# dlp_vco_v1_1_4_pnl.net
KiCad netlist of a schematic drawn in EAGLE
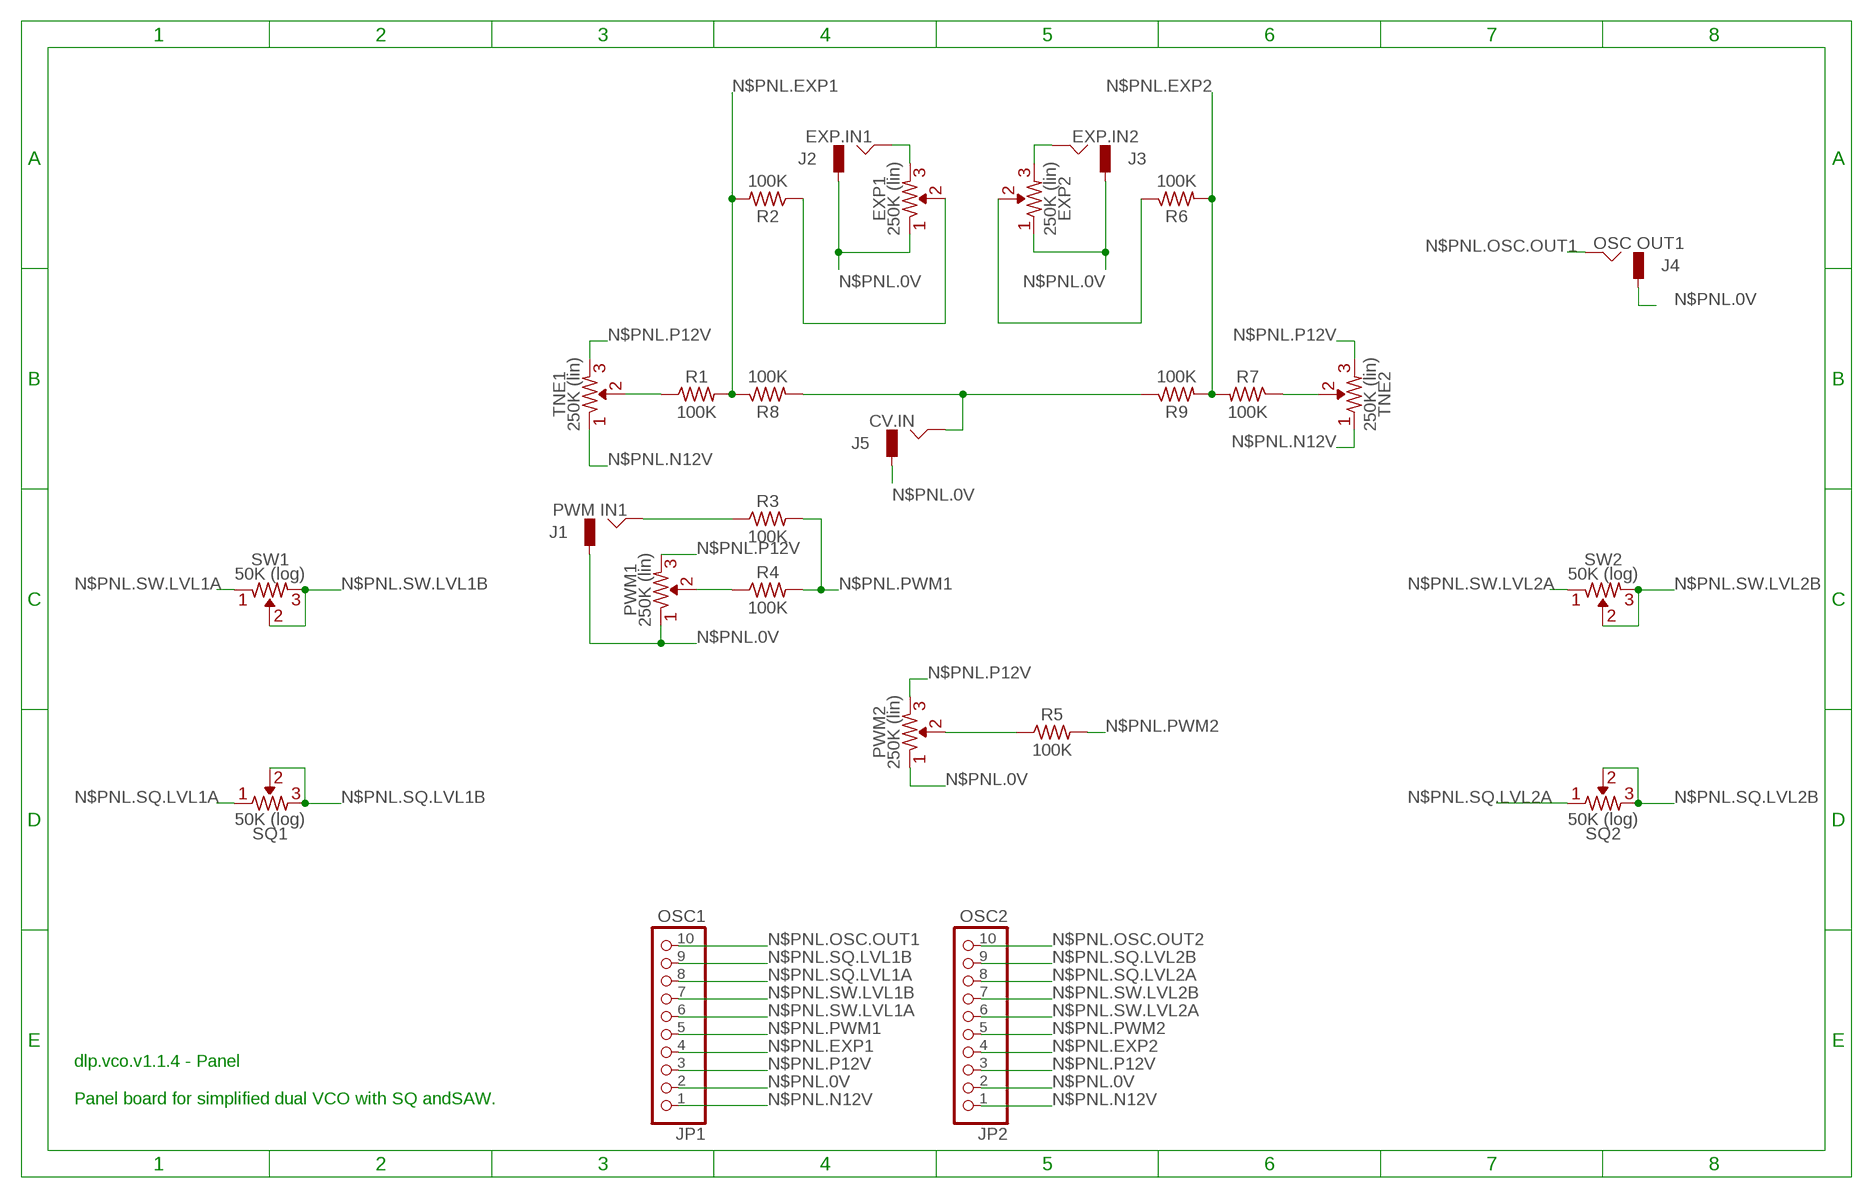
[diagram p0: schematic, sheet 1]

(export (version "E")
  (design (tool "Eeschema 10.0.6"))
  (components
    (comp (ref "EXP1")
      (value "250K (lin)")
      (footprint "eagle-import:R-VAR")
      (libsource (lib "eagle-import") (part "R-VAR"))
    )
    (comp (ref "EXP2")
      (value "250K (lin)")
      (footprint "eagle-import:R-VAR")
      (libsource (lib "eagle-import") (part "R-VAR"))
    )
    (comp (ref "J1")
      (value "PWM IN1")
      (footprint "eagle-import:JACK-M")
      (libsource (lib "eagle-import") (part "JACK-M"))
    )
    (comp (ref "J2")
      (value "EXP.IN1")
      (footprint "eagle-import:JACK-M")
      (libsource (lib "eagle-import") (part "JACK-M"))
    )
    (comp (ref "J3")
      (value "EXP.IN2")
      (footprint "eagle-import:JACK-M")
      (libsource (lib "eagle-import") (part "JACK-M"))
    )
    (comp (ref "J4")
      (value "OSC OUT1")
      (footprint "eagle-import:JACK-M")
      (libsource (lib "eagle-import") (part "JACK-M"))
    )
    (comp (ref "J5")
      (value "CV.IN")
      (footprint "eagle-import:JACK-M")
      (libsource (lib "eagle-import") (part "JACK-M"))
    )
    (comp (ref "JP1")
      (value "OSC1")
      (footprint "eagle-import:1X10")
      (libsource (lib "eagle-import") (part "PINHD-1X10"))
    )
    (comp (ref "JP2")
      (value "OSC2")
      (footprint "eagle-import:1X10")
      (libsource (lib "eagle-import") (part "PINHD-1X10"))
    )
    (comp (ref "PWM1")
      (value "250K (lin)")
      (footprint "eagle-import:R-VAR")
      (libsource (lib "eagle-import") (part "R-VAR"))
    )
    (comp (ref "PWM2")
      (value "250K (lin)")
      (footprint "eagle-import:R-VAR")
      (libsource (lib "eagle-import") (part "R-VAR"))
    )
    (comp (ref "R1")
      (value "100K")
      (footprint "eagle-import:0309_10")
      (libsource (lib "eagle-import") (part "R0309/10"))
    )
    (comp (ref "R2")
      (value "100K")
      (footprint "eagle-import:0309_10")
      (libsource (lib "eagle-import") (part "R0309/10"))
    )
    (comp (ref "R3")
      (value "100K")
      (footprint "eagle-import:0309_10")
      (libsource (lib "eagle-import") (part "R0309/10"))
    )
    (comp (ref "R4")
      (value "100K")
      (footprint "eagle-import:0309_10")
      (libsource (lib "eagle-import") (part "R0309/10"))
    )
    (comp (ref "R5")
      (value "100K")
      (footprint "eagle-import:0309_10")
      (libsource (lib "eagle-import") (part "R0309/10"))
    )
    (comp (ref "R6")
      (value "100K")
      (footprint "eagle-import:0309_10")
      (libsource (lib "eagle-import") (part "R0309/10"))
    )
    (comp (ref "R7")
      (value "100K")
      (footprint "eagle-import:0309_10")
      (libsource (lib "eagle-import") (part "R0309/10"))
    )
    (comp (ref "R8")
      (value "100K")
      (footprint "eagle-import:0309_10")
      (libsource (lib "eagle-import") (part "R0309/10"))
    )
    (comp (ref "R9")
      (value "100K")
      (footprint "eagle-import:0309_10")
      (libsource (lib "eagle-import") (part "R0309/10"))
    )
    (comp (ref "SQ1")
      (value "50K (log)")
      (footprint "eagle-import:R-VAR")
      (libsource (lib "eagle-import") (part "R-VAR"))
    )
    (comp (ref "SQ2")
      (value "50K (log)")
      (footprint "eagle-import:R-VAR")
      (libsource (lib "eagle-import") (part "R-VAR"))
    )
    (comp (ref "SW1")
      (value "50K (log)")
      (footprint "eagle-import:R-VAR")
      (libsource (lib "eagle-import") (part "R-VAR"))
    )
    (comp (ref "SW2")
      (value "50K (log)")
      (footprint "eagle-import:R-VAR")
      (libsource (lib "eagle-import") (part "R-VAR"))
    )
    (comp (ref "TNE1")
      (value "250K (lin)")
      (footprint "eagle-import:R-VAR")
      (libsource (lib "eagle-import") (part "R-VAR"))
    )
    (comp (ref "TNE2")
      (value "250K (lin)")
      (footprint "eagle-import:R-VAR")
      (libsource (lib "eagle-import") (part "R-VAR"))
    )
  )
  (nets
    (net (code "1") (name "/N$PNL.0V") (class "Default")
      (node (ref "EXP1") (pin "R1") (pinfunction "1_R1") (pintype "passive"))
      (node (ref "EXP2") (pin "R1") (pinfunction "1_R1") (pintype "passive"))
      (node (ref "J1") (pin "GND") (pinfunction "GND_GND") (pintype "bidirectional"))
      (node (ref "J2") (pin "GND") (pinfunction "GND_GND") (pintype "bidirectional"))
      (node (ref "J3") (pin "GND") (pinfunction "GND_GND") (pintype "bidirectional"))
      (node (ref "J4") (pin "GND") (pinfunction "GND_GND") (pintype "bidirectional"))
      (node (ref "J5") (pin "GND") (pinfunction "GND_GND") (pintype "bidirectional"))
      (node (ref "JP1") (pin "2") (pinfunction "2_2") (pintype "passive"))
      (node (ref "JP2") (pin "2") (pinfunction "2_2") (pintype "passive"))
      (node (ref "PWM1") (pin "R1") (pinfunction "1_R1") (pintype "passive"))
      (node (ref "PWM2") (pin "R1") (pinfunction "1_R1") (pintype "passive"))
    )
    (net (code "2") (name "/N$PNL.EXP1") (class "Default")
      (node (ref "JP1") (pin "4") (pinfunction "4_4") (pintype "passive"))
      (node (ref "R1") (pin "2") (pinfunction "2_2") (pintype "passive"))
      (node (ref "R2") (pin "2") (pinfunction "2_2") (pintype "passive"))
      (node (ref "R8") (pin "1") (pinfunction "1_1") (pintype "passive"))
    )
    (net (code "3") (name "/N$PNL.EXP2") (class "Default")
      (node (ref "JP2") (pin "4") (pinfunction "4_4") (pintype "passive"))
      (node (ref "R6") (pin "2") (pinfunction "2_2") (pintype "passive"))
      (node (ref "R7") (pin "2") (pinfunction "2_2") (pintype "passive"))
      (node (ref "R9") (pin "2") (pinfunction "2_2") (pintype "passive"))
    )
    (net (code "4") (name "/N$PNL.N12V") (class "Default")
      (node (ref "JP1") (pin "1") (pinfunction "1_1") (pintype "passive"))
      (node (ref "JP2") (pin "1") (pinfunction "1_1") (pintype "passive"))
      (node (ref "TNE1") (pin "R1") (pinfunction "1_R1") (pintype "passive"))
      (node (ref "TNE2") (pin "R1") (pinfunction "1_R1") (pintype "passive"))
    )
    (net (code "5") (name "/N$PNL.OSC.OUT1") (class "Default")
      (node (ref "J4") (pin "HOT") (pinfunction "HOT_HOT") (pintype "bidirectional"))
      (node (ref "JP1") (pin "10") (pinfunction "10_10") (pintype "passive"))
    )
    (net (code "6") (name "/N$PNL.OSC.OUT2") (class "Default")
      (node (ref "JP2") (pin "10") (pinfunction "10_10") (pintype "passive"))
    )
    (net (code "7") (name "/N$PNL.P12V") (class "Default")
      (node (ref "JP1") (pin "3") (pinfunction "3_3") (pintype "passive"))
      (node (ref "JP2") (pin "3") (pinfunction "3_3") (pintype "passive"))
      (node (ref "PWM1") (pin "R2") (pinfunction "2_R2") (pintype "passive"))
      (node (ref "PWM2") (pin "R2") (pinfunction "2_R2") (pintype "passive"))
      (node (ref "TNE1") (pin "R2") (pinfunction "2_R2") (pintype "passive"))
      (node (ref "TNE2") (pin "R2") (pinfunction "2_R2") (pintype "passive"))
    )
    (net (code "8") (name "/N$PNL.PWM1") (class "Default")
      (node (ref "JP1") (pin "5") (pinfunction "5_5") (pintype "passive"))
      (node (ref "R3") (pin "2") (pinfunction "2_2") (pintype "passive"))
      (node (ref "R4") (pin "2") (pinfunction "2_2") (pintype "passive"))
    )
    (net (code "9") (name "/N$PNL.PWM2") (class "Default")
      (node (ref "JP2") (pin "5") (pinfunction "5_5") (pintype "passive"))
      (node (ref "R5") (pin "2") (pinfunction "2_2") (pintype "passive"))
    )
    (net (code "10") (name "/N$PNL.SQ.LVL1A") (class "Default")
      (node (ref "JP1") (pin "8") (pinfunction "8_8") (pintype "passive"))
      (node (ref "SQ1") (pin "R1") (pinfunction "1_R1") (pintype "passive"))
    )
    (net (code "11") (name "/N$PNL.SQ.LVL1B") (class "Default")
      (node (ref "JP1") (pin "9") (pinfunction "9_9") (pintype "passive"))
      (node (ref "SQ1") (pin "R2") (pinfunction "2_R2") (pintype "passive"))
      (node (ref "SQ1") (pin "VAR") (pinfunction "P$1_VAR") (pintype "passive"))
    )
    (net (code "12") (name "/N$PNL.SQ.LVL2A") (class "Default")
      (node (ref "JP2") (pin "8") (pinfunction "8_8") (pintype "passive"))
      (node (ref "SQ2") (pin "R1") (pinfunction "1_R1") (pintype "passive"))
    )
    (net (code "13") (name "/N$PNL.SQ.LVL2B") (class "Default")
      (node (ref "JP2") (pin "9") (pinfunction "9_9") (pintype "passive"))
      (node (ref "SQ2") (pin "R2") (pinfunction "2_R2") (pintype "passive"))
      (node (ref "SQ2") (pin "VAR") (pinfunction "P$1_VAR") (pintype "passive"))
    )
    (net (code "14") (name "/N$PNL.SW.LVL1A") (class "Default")
      (node (ref "JP1") (pin "6") (pinfunction "6_6") (pintype "passive"))
      (node (ref "SW1") (pin "R1") (pinfunction "1_R1") (pintype "passive"))
    )
    (net (code "15") (name "/N$PNL.SW.LVL1B") (class "Default")
      (node (ref "JP1") (pin "7") (pinfunction "7_7") (pintype "passive"))
      (node (ref "SW1") (pin "R2") (pinfunction "2_R2") (pintype "passive"))
      (node (ref "SW1") (pin "VAR") (pinfunction "P$1_VAR") (pintype "passive"))
    )
    (net (code "16") (name "/N$PNL.SW.LVL2A") (class "Default")
      (node (ref "JP2") (pin "6") (pinfunction "6_6") (pintype "passive"))
      (node (ref "SW2") (pin "R1") (pinfunction "1_R1") (pintype "passive"))
    )
    (net (code "17") (name "/N$PNL.SW.LVL2B") (class "Default")
      (node (ref "JP2") (pin "7") (pinfunction "7_7") (pintype "passive"))
      (node (ref "SW2") (pin "R2") (pinfunction "2_R2") (pintype "passive"))
      (node (ref "SW2") (pin "VAR") (pinfunction "P$1_VAR") (pintype "passive"))
    )
    (net (code "18") (name "Net-(EXP1-2)") (class "Default")
      (node (ref "EXP1") (pin "R2") (pinfunction "2_R2") (pintype "passive"))
      (node (ref "J2") (pin "HOT") (pinfunction "HOT_HOT") (pintype "bidirectional"))
    )
    (net (code "19") (name "Net-(EXP1-P$1)") (class "Default")
      (node (ref "EXP1") (pin "VAR") (pinfunction "P$1_VAR") (pintype "passive"))
      (node (ref "R2") (pin "1") (pinfunction "1_1") (pintype "passive"))
    )
    (net (code "20") (name "Net-(EXP2-2)") (class "Default")
      (node (ref "EXP2") (pin "R2") (pinfunction "2_R2") (pintype "passive"))
      (node (ref "J3") (pin "HOT") (pinfunction "HOT_HOT") (pintype "bidirectional"))
    )
    (net (code "21") (name "Net-(EXP2-P$1)") (class "Default")
      (node (ref "EXP2") (pin "VAR") (pinfunction "P$1_VAR") (pintype "passive"))
      (node (ref "R6") (pin "1") (pinfunction "1_1") (pintype "passive"))
    )
    (net (code "22") (name "Net-(J1-PadHOT)") (class "Default")
      (node (ref "J1") (pin "HOT") (pinfunction "HOT_HOT") (pintype "bidirectional"))
      (node (ref "R3") (pin "1") (pinfunction "1_1") (pintype "passive"))
    )
    (net (code "23") (name "Net-(J5-PadHOT)") (class "Default")
      (node (ref "J5") (pin "HOT") (pinfunction "HOT_HOT") (pintype "bidirectional"))
      (node (ref "R8") (pin "2") (pinfunction "2_2") (pintype "passive"))
      (node (ref "R9") (pin "1") (pinfunction "1_1") (pintype "passive"))
    )
    (net (code "24") (name "Net-(PWM1-P$1)") (class "Default")
      (node (ref "PWM1") (pin "VAR") (pinfunction "P$1_VAR") (pintype "passive"))
      (node (ref "R4") (pin "1") (pinfunction "1_1") (pintype "passive"))
    )
    (net (code "25") (name "Net-(PWM2-P$1)") (class "Default")
      (node (ref "PWM2") (pin "VAR") (pinfunction "P$1_VAR") (pintype "passive"))
      (node (ref "R5") (pin "1") (pinfunction "1_1") (pintype "passive"))
    )
    (net (code "26") (name "Net-(TNE1-P$1)") (class "Default")
      (node (ref "R1") (pin "1") (pinfunction "1_1") (pintype "passive"))
      (node (ref "TNE1") (pin "VAR") (pinfunction "P$1_VAR") (pintype "passive"))
    )
    (net (code "27") (name "Net-(TNE2-P$1)") (class "Default")
      (node (ref "R7") (pin "1") (pinfunction "1_1") (pintype "passive"))
      (node (ref "TNE2") (pin "VAR") (pinfunction "P$1_VAR") (pintype "passive"))
    )
  )
)
